# axiom_beta_power_adapter_v0_1_63a69e4d.net
KiCad netlist of a schematic drawn in EAGLE
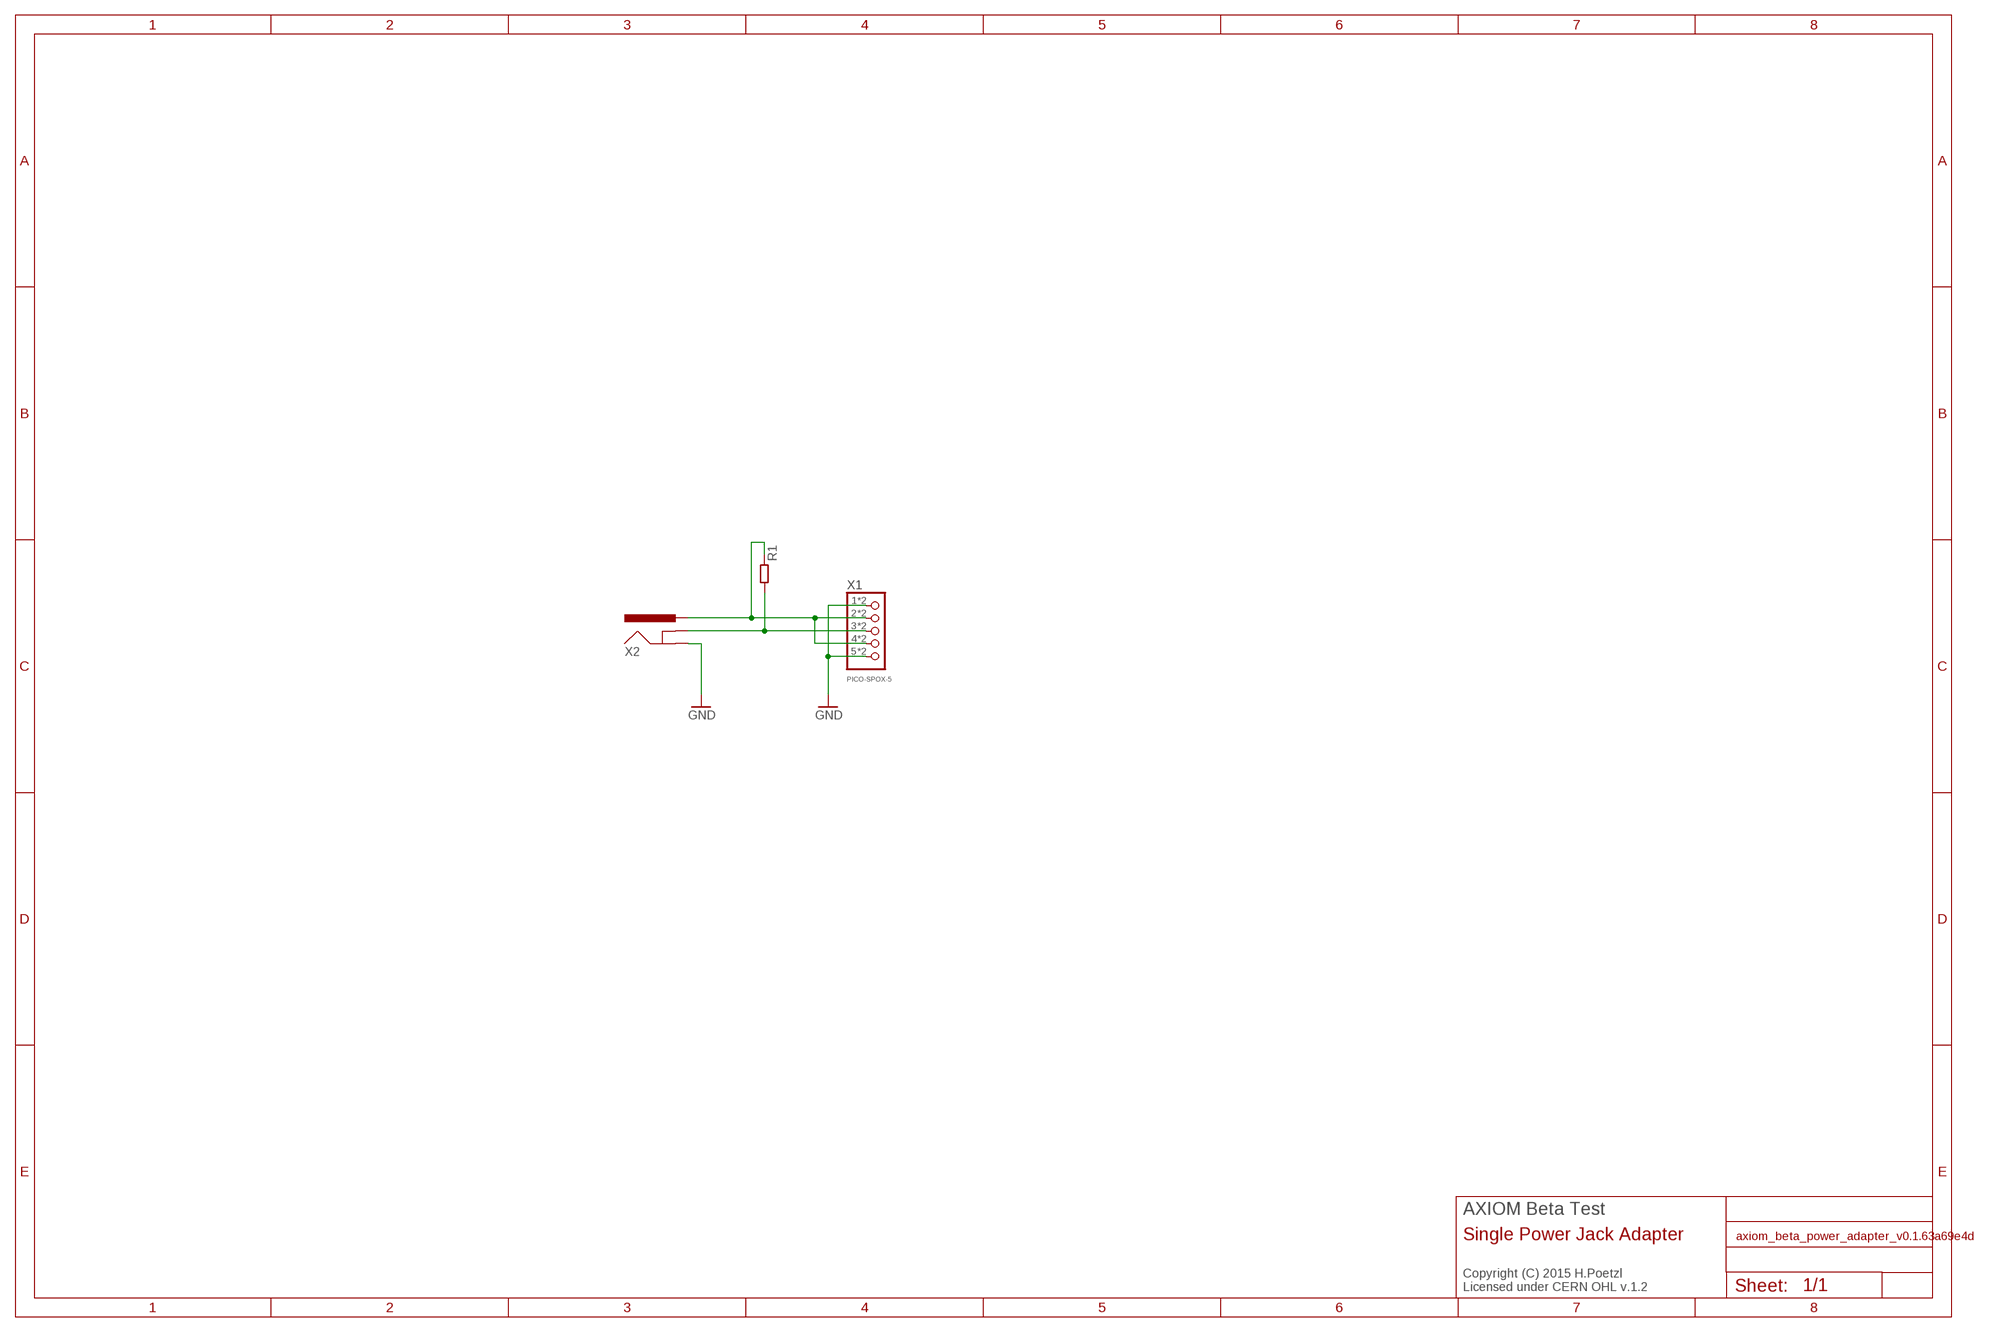
[diagram p0: schematic, sheet 1]

(export (version "E")
  (design (tool "Eeschema 10.0.6"))
  (components
    (comp (ref "R1")
      (value "R0402-B")
      (footprint "eagle-import:0402-B")
      (libsource (lib "eagle-import") (part "R0402-B"))
    )
    (comp (ref "X1")
      (value "PICO-SPOX-5")
      (footprint "eagle-import:PICO-SPOX-5")
      (libsource (lib "eagle-import") (part "PICO-SPOX-5"))
    )
    (comp (ref "X2")
      (value "POWER_JACKPTH")
      (footprint "eagle-import:POWER_JACK_PTH")
      (libsource (lib "eagle-import") (part "POWER_JACKPTH"))
    )
  )
  (nets
    (net (code "1") (name "GND") (class "Default")
      (node (ref "X1") (pin "1") (pinfunction "1_1") (pintype "passive"))
      (node (ref "X1") (pin "1A") (pinfunction "1_1A") (pintype "passive"))
      (node (ref "X1") (pin "5") (pinfunction "5_5") (pintype "passive"))
      (node (ref "X1") (pin "5A") (pinfunction "5_5A") (pintype "passive"))
      (node (ref "X2") (pin "GND") (pinfunction "GND_GND") (pintype "bidirectional"))
    )
    (net (code "2") (name "Net-(R1-Pad1)") (class "Default")
      (node (ref "R1") (pin "1") (pinfunction "1_1") (pintype "passive"))
      (node (ref "X1") (pin "2") (pinfunction "2_2") (pintype "passive"))
      (node (ref "X1") (pin "2A") (pinfunction "2_2A") (pintype "passive"))
      (node (ref "X1") (pin "4") (pinfunction "4_4") (pintype "passive"))
      (node (ref "X1") (pin "4A") (pinfunction "4_4A") (pintype "passive"))
      (node (ref "X2") (pin "PWR") (pinfunction "PWR_PWR") (pintype "bidirectional"))
    )
    (net (code "3") (name "Net-(X2-GNDBREAK)") (class "Default")
      (node (ref "R1") (pin "2") (pinfunction "2_2") (pintype "passive"))
      (node (ref "X1") (pin "3") (pinfunction "3_3") (pintype "passive"))
      (node (ref "X1") (pin "3A") (pinfunction "3_3A") (pintype "passive"))
      (node (ref "X2") (pin "SHUNT") (pinfunction "GNDBREAK_SHUNT") (pintype "bidirectional"))
    )
  )
)
